# Sensor.net
KiCad netlist of a schematic drawn in Altium Designer
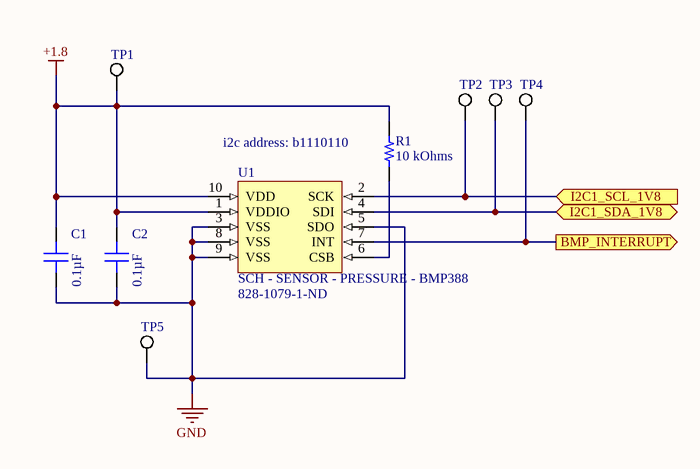
[diagram p0: Sensor.SchDoc]

(export (version "E")
  (design (tool "Eeschema 10.0.6"))
  (components
    (comp (ref "C1")
      (value "0.1µF")
      (footprint "CAP 0603_1608")
      (description "CAP CER 0.1UF 25V X7R 0603")
      (fields
        (field (name "PART NUMBER") "CL10B104KA8WPNC")
        (field (name "MANUFACTURER") "Samsung Electro-Mechanics")
      )
      (libsource (lib "Celestial Altium Library - altium_library") (part "Capacitor"))
    )
    (comp (ref "C2")
      (value "0.1µF")
      (footprint "CAP 0603_1608")
      (description "CAP CER 0.1UF 25V X7R 0603")
      (fields
        (field (name "PART NUMBER") "CL10B104KA8WPNC")
        (field (name "MANUFACTURER") "Samsung Electro-Mechanics")
      )
      (libsource (lib "Celestial Altium Library - altium_library") (part "Capacitor"))
    )
    (comp (ref "R1")
      (value "10 kOhms")
      (footprint "RES 0603_1608")
      (description "RES 10K OHM 5% 1/10W 0603")
      (fields
        (field (name "PART NUMBER") "RMCF0603JT10K0")
        (field (name "MANUFACTURER") "Stackpole Electronics Inc")
      )
      (libsource (lib "Celestial Altium Library - altium_library") (part "Resistor"))
    )
    (comp (ref "TP1")
      (value "5019")
      (footprint "KSTN-5019_V")
      (description "Test Point, 1 Position SMD, RoHS, Tape and Reel")
      (libsource (lib "Altium Content Vault") (part "TESTPOINT_WHITE"))
    )
    (comp (ref "TP2")
      (value "5019")
      (footprint "KSTN-5019_V")
      (description "Test Point, 1 Position SMD, RoHS, Tape and Reel")
      (libsource (lib "Altium Content Vault") (part "TESTPOINT_WHITE"))
    )
    (comp (ref "TP3")
      (value "5019")
      (footprint "KSTN-5019_V")
      (description "Test Point, 1 Position SMD, RoHS, Tape and Reel")
      (libsource (lib "Altium Content Vault") (part "TESTPOINT_WHITE"))
    )
    (comp (ref "TP4")
      (value "5019")
      (footprint "KSTN-5019_V")
      (description "Test Point, 1 Position SMD, RoHS, Tape and Reel")
      (libsource (lib "Altium Content Vault") (part "TESTPOINT_WHITE"))
    )
    (comp (ref "TP5")
      (value "5019")
      (footprint "KSTN-5019_V")
      (description "Test Point, 1 Position SMD, RoHS, Tape and Reel")
      (libsource (lib "Altium Content Vault") (part "TESTPOINT_WHITE"))
    )
    (comp (ref "U1")
      (value "SCH - SENSOR - PRESSURE - BMP388")
      (footprint "PCB - LEADLESS - BOSCH LGA10")
      (fields (field (name "SUPPLIER PART NUMBER 1") "828-1079-1-ND"))
      (libsource (lib "HAB_ICs") (part "SCH - SENSOR - PRESSURE - BMP388"))
    )
  )
  (nets
    (net (code "1") (name "+1.8") (class "Default")
      (node (ref "C1") (pin "2") (pinfunction "2_2") (pintype "passive"))
      (node (ref "C2") (pin "2") (pinfunction "2_2") (pintype "passive"))
      (node (ref "R1") (pin "1") (pinfunction "1_1") (pintype "passive"))
      (node (ref "TP1") (pin "1") (pinfunction "1_1") (pintype "passive"))
      (node (ref "U1") (pin "1") (pinfunction "VDDIO_1") (pintype "input"))
      (node (ref "U1") (pin "10") (pinfunction "VDD_10") (pintype "input"))
    )
    (net (code "2") (name "/BMP_INTERRUPT") (class "Default")
      (node (ref "TP4") (pin "1") (pinfunction "1_1") (pintype "passive"))
      (node (ref "U1") (pin "7") (pinfunction "INT_7") (pintype "input"))
    )
    (net (code "3") (name "/I2C1_SCL_1V8") (class "Default")
      (node (ref "TP2") (pin "1") (pinfunction "1_1") (pintype "passive"))
      (node (ref "U1") (pin "2") (pinfunction "SCK_2") (pintype "input"))
    )
    (net (code "4") (name "/I2C1_SDA_1V8") (class "Default")
      (node (ref "TP3") (pin "1") (pinfunction "1_1") (pintype "passive"))
      (node (ref "U1") (pin "4") (pinfunction "SDI_4") (pintype "input"))
    )
    (net (code "5") (name "GND") (class "Default")
      (node (ref "C1") (pin "1") (pinfunction "1_1") (pintype "passive"))
      (node (ref "C2") (pin "1") (pinfunction "1_1") (pintype "passive"))
      (node (ref "TP5") (pin "1") (pinfunction "1_1") (pintype "passive"))
      (node (ref "U1") (pin "3") (pinfunction "VSS_3") (pintype "input"))
      (node (ref "U1") (pin "5") (pinfunction "SDO_5") (pintype "input"))
      (node (ref "U1") (pin "8") (pinfunction "VSS_8") (pintype "input"))
      (node (ref "U1") (pin "9") (pinfunction "VSS_9") (pintype "input"))
    )
    (net (code "6") (name "Net-(U1-CSB)") (class "Default")
      (node (ref "R1") (pin "2") (pinfunction "2_2") (pintype "passive"))
      (node (ref "U1") (pin "6") (pinfunction "CSB_6") (pintype "input"))
    )
  )
)
